# analog_pitch_board.net
KiCad netlist of a schematic drawn in EAGLE
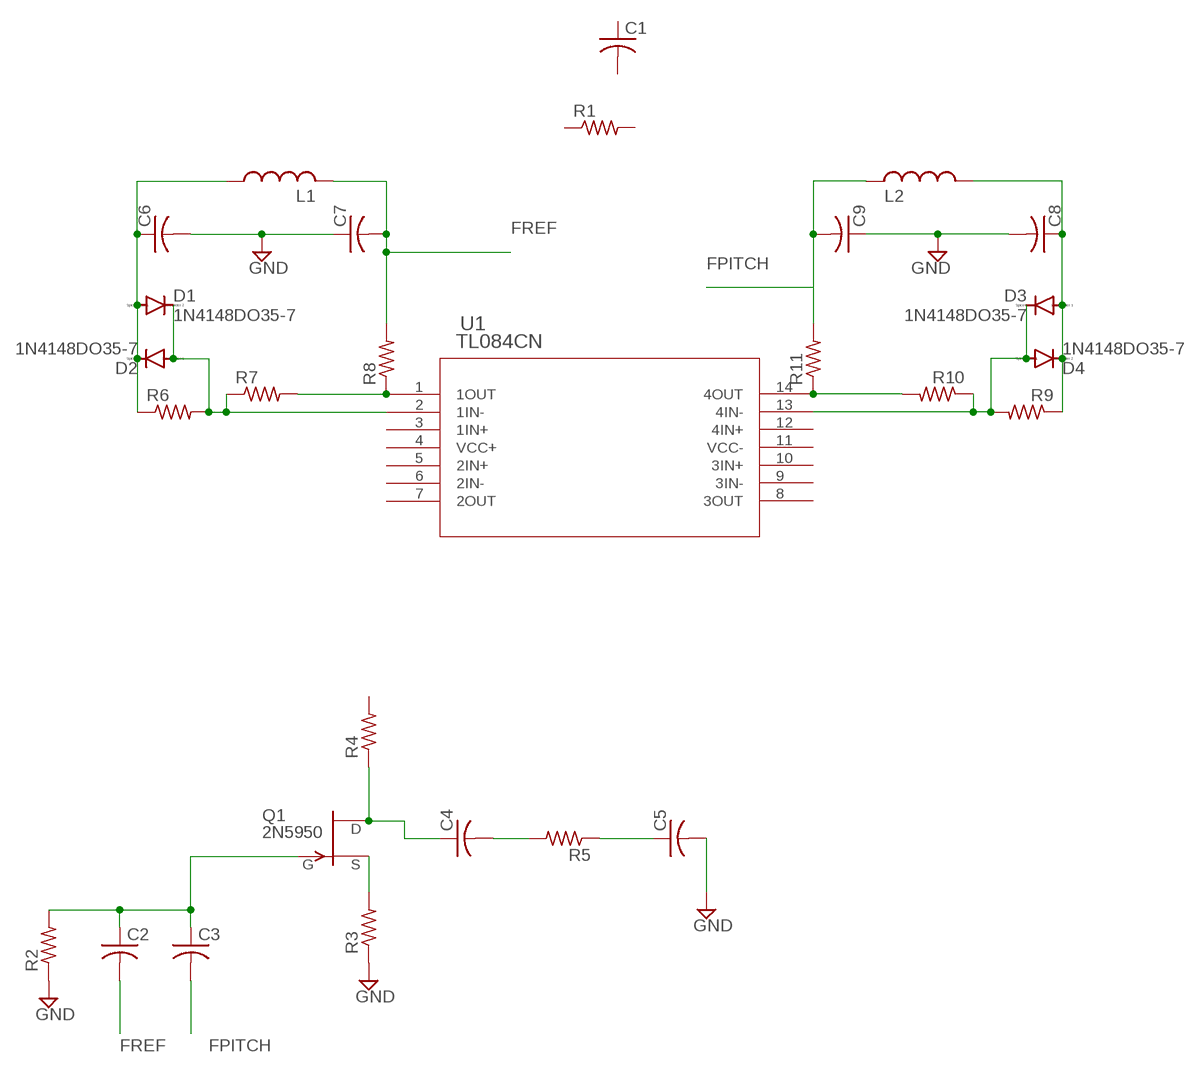
[diagram p0: schematic, sheet 1]

(export (version "E")
  (design (tool "Eeschema 10.0.6"))
  (components
    (comp (ref "C1")
      (value "C-US025-024X044")
      (footprint "eagle-import:C025-024X044")
      (libsource (lib "eagle-import") (part "C-US025-024X044"))
    )
    (comp (ref "C2")
      (value "C-US025-024X044")
      (footprint "eagle-import:C025-024X044")
      (libsource (lib "eagle-import") (part "C-US025-024X044"))
    )
    (comp (ref "C3")
      (value "C-US025-024X044")
      (footprint "eagle-import:C025-024X044")
      (libsource (lib "eagle-import") (part "C-US025-024X044"))
    )
    (comp (ref "C4")
      (value "C-US025-024X044")
      (footprint "eagle-import:C025-024X044")
      (libsource (lib "eagle-import") (part "C-US025-024X044"))
    )
    (comp (ref "C5")
      (value "C-US025-024X044")
      (footprint "eagle-import:C025-024X044")
      (libsource (lib "eagle-import") (part "C-US025-024X044"))
    )
    (comp (ref "C6")
      (value "C-US025-024X044")
      (footprint "eagle-import:C025-024X044")
      (libsource (lib "eagle-import") (part "C-US025-024X044"))
    )
    (comp (ref "C7")
      (value "C-US025-024X044")
      (footprint "eagle-import:C025-024X044")
      (libsource (lib "eagle-import") (part "C-US025-024X044"))
    )
    (comp (ref "C8")
      (value "C-US025-024X044")
      (footprint "eagle-import:C025-024X044")
      (libsource (lib "eagle-import") (part "C-US025-024X044"))
    )
    (comp (ref "C9")
      (value "C-US025-024X044")
      (footprint "eagle-import:C025-024X044")
      (libsource (lib "eagle-import") (part "C-US025-024X044"))
    )
    (comp (ref "D1")
      (value "1N4148DO35-7")
      (footprint "eagle-import:DO35-7")
      (libsource (lib "eagle-import") (part "1N4148DO35-7"))
    )
    (comp (ref "D2")
      (value "1N4148DO35-7")
      (footprint "eagle-import:DO35-7")
      (libsource (lib "eagle-import") (part "1N4148DO35-7"))
    )
    (comp (ref "D3")
      (value "1N4148DO35-7")
      (footprint "eagle-import:DO35-7")
      (libsource (lib "eagle-import") (part "1N4148DO35-7"))
    )
    (comp (ref "D4")
      (value "1N4148DO35-7")
      (footprint "eagle-import:DO35-7")
      (libsource (lib "eagle-import") (part "1N4148DO35-7"))
    )
    (comp (ref "L1")
      (value "L-US6000-XXX-RC")
      (footprint "eagle-import:6000-XXXX-RC")
      (libsource (lib "eagle-import") (part "L-US6000-XXX-RC"))
    )
    (comp (ref "L2")
      (value "L-US6000-XXX-RC")
      (footprint "eagle-import:6000-XXXX-RC")
      (libsource (lib "eagle-import") (part "L-US6000-XXX-RC"))
    )
    (comp (ref "Q1")
      (value "2N5950")
      (footprint "eagle-import:TO-92")
      (libsource (lib "eagle-import") (part "2N5950"))
    )
    (comp (ref "R1")
      (value "R-US_0207/10")
      (footprint "eagle-import:0207_10")
      (libsource (lib "eagle-import") (part "R-US_0207/10"))
    )
    (comp (ref "R2")
      (value "R-US_0207/10")
      (footprint "eagle-import:0207_10")
      (libsource (lib "eagle-import") (part "R-US_0207/10"))
    )
    (comp (ref "R3")
      (value "R-US_0207/10")
      (footprint "eagle-import:0207_10")
      (libsource (lib "eagle-import") (part "R-US_0207/10"))
    )
    (comp (ref "R4")
      (value "R-US_0207/10")
      (footprint "eagle-import:0207_10")
      (libsource (lib "eagle-import") (part "R-US_0207/10"))
    )
    (comp (ref "R5")
      (value "R-US_0207/10")
      (footprint "eagle-import:0207_10")
      (libsource (lib "eagle-import") (part "R-US_0207/10"))
    )
    (comp (ref "R6")
      (value "R-US_0207/10")
      (footprint "eagle-import:0207_10")
      (libsource (lib "eagle-import") (part "R-US_0207/10"))
    )
    (comp (ref "R7")
      (value "R-US_0207/10")
      (footprint "eagle-import:0207_10")
      (libsource (lib "eagle-import") (part "R-US_0207/10"))
    )
    (comp (ref "R8")
      (value "R-US_0207/10")
      (footprint "eagle-import:0207_10")
      (libsource (lib "eagle-import") (part "R-US_0207/10"))
    )
    (comp (ref "R9")
      (value "R-US_0207/10")
      (footprint "eagle-import:0207_10")
      (libsource (lib "eagle-import") (part "R-US_0207/10"))
    )
    (comp (ref "R10")
      (value "R-US_0207/10")
      (footprint "eagle-import:0207_10")
      (libsource (lib "eagle-import") (part "R-US_0207/10"))
    )
    (comp (ref "R11")
      (value "R-US_0207/10")
      (footprint "eagle-import:0207_10")
      (libsource (lib "eagle-import") (part "R-US_0207/10"))
    )
    (comp (ref "U1")
      (value "TL084CN")
      (footprint "eagle-import:N14")
      (fields (field (name "COPYRIGHT") "Copyright (C) 2025 Ultra Librarian. All rights reserved."))
      (libsource (lib "eagle-import") (part "TL084CN"))
    )
  )
  (nets
    (net (code "1") (name "/FPITCH") (class "Default")
      (node (ref "C3") (pin "2") (pinfunction "2_2") (pintype "passive"))
      (node (ref "C9") (pin "2") (pinfunction "2_2") (pintype "passive"))
      (node (ref "L2") (pin "2") (pinfunction "2_2") (pintype "passive"))
      (node (ref "R11") (pin "2") (pinfunction "2_2") (pintype "passive"))
    )
    (net (code "2") (name "/FREF") (class "Default")
      (node (ref "C2") (pin "2") (pinfunction "2_2") (pintype "passive"))
      (node (ref "C7") (pin "2") (pinfunction "2_2") (pintype "passive"))
      (node (ref "L1") (pin "2") (pinfunction "2_2") (pintype "passive"))
      (node (ref "R8") (pin "2") (pinfunction "2_2") (pintype "passive"))
    )
    (net (code "3") (name "/VCC+") (class "Default")
      (node (ref "U1") (pin "4") (pinfunction "VCC+_4") (pintype "power_in"))
    )
    (net (code "4") (name "/VCC-") (class "Default")
      (node (ref "U1") (pin "11") (pinfunction "VCC-_11") (pintype "power_in"))
    )
    (net (code "5") (name "GND") (class "Default")
      (node (ref "C5") (pin "2") (pinfunction "2_2") (pintype "passive"))
      (node (ref "C6") (pin "2") (pinfunction "2_2") (pintype "passive"))
      (node (ref "C7") (pin "1") (pinfunction "1_1") (pintype "passive"))
      (node (ref "C8") (pin "2") (pinfunction "2_2") (pintype "passive"))
      (node (ref "C9") (pin "1") (pinfunction "1_1") (pintype "passive"))
      (node (ref "R2") (pin "1") (pinfunction "1_1") (pintype "passive"))
      (node (ref "R3") (pin "1") (pinfunction "1_1") (pintype "passive"))
    )
    (net (code "6") (name "Net-(C4-Pad2)") (class "Default")
      (node (ref "C4") (pin "2") (pinfunction "2_2") (pintype "passive"))
      (node (ref "R5") (pin "2") (pinfunction "2_2") (pintype "passive"))
    )
    (net (code "7") (name "Net-(C5-Pad1)") (class "Default")
      (node (ref "C5") (pin "1") (pinfunction "1_1") (pintype "passive"))
      (node (ref "R5") (pin "1") (pinfunction "1_1") (pintype "passive"))
    )
    (net (code "8") (name "Net-(C6-Pad1)") (class "Default")
      (node (ref "C6") (pin "1") (pinfunction "1_1") (pintype "passive"))
      (node (ref "D1") (pin "A") (pinfunction "A_A") (pintype "passive"))
      (node (ref "D2") (pin "C") (pinfunction "C_C") (pintype "passive"))
      (node (ref "L1") (pin "1") (pinfunction "1_1") (pintype "passive"))
      (node (ref "R6") (pin "1") (pinfunction "1_1") (pintype "passive"))
    )
    (net (code "9") (name "Net-(C8-Pad1)") (class "Default")
      (node (ref "C8") (pin "1") (pinfunction "1_1") (pintype "passive"))
      (node (ref "D3") (pin "A") (pinfunction "A_A") (pintype "passive"))
      (node (ref "D4") (pin "C") (pinfunction "C_C") (pintype "passive"))
      (node (ref "L2") (pin "1") (pinfunction "1_1") (pintype "passive"))
      (node (ref "R9") (pin "1") (pinfunction "1_1") (pintype "passive"))
    )
    (net (code "10") (name "Net-(Q1-D)") (class "Default")
      (node (ref "C4") (pin "1") (pinfunction "1_1") (pintype "passive"))
      (node (ref "Q1") (pin "3") (pinfunction "D_3") (pintype "passive"))
      (node (ref "R4") (pin "1") (pinfunction "1_1") (pintype "passive"))
    )
    (net (code "11") (name "Net-(Q1-G)") (class "Default")
      (node (ref "C2") (pin "1") (pinfunction "1_1") (pintype "passive"))
      (node (ref "C3") (pin "1") (pinfunction "1_1") (pintype "passive"))
      (node (ref "Q1") (pin "1") (pinfunction "G_1") (pintype "passive"))
      (node (ref "R2") (pin "2") (pinfunction "2_2") (pintype "passive"))
    )
    (net (code "12") (name "Net-(Q1-S)") (class "Default")
      (node (ref "Q1") (pin "2") (pinfunction "S_2") (pintype "passive"))
      (node (ref "R3") (pin "2") (pinfunction "2_2") (pintype "passive"))
    )
    (net (code "13") (name "Net-(U1-1IN-)") (class "Default")
      (node (ref "D1") (pin "C") (pinfunction "C_C") (pintype "passive"))
      (node (ref "D2") (pin "A") (pinfunction "A_A") (pintype "passive"))
      (node (ref "R6") (pin "2") (pinfunction "2_2") (pintype "passive"))
      (node (ref "R7") (pin "1") (pinfunction "1_1") (pintype "passive"))
      (node (ref "U1") (pin "2") (pinfunction "1IN-_2") (pintype "input"))
    )
    (net (code "14") (name "Net-(U1-1OUT)") (class "Default")
      (node (ref "R7") (pin "2") (pinfunction "2_2") (pintype "passive"))
      (node (ref "R8") (pin "1") (pinfunction "1_1") (pintype "passive"))
      (node (ref "U1") (pin "1") (pinfunction "1OUT_1") (pintype "output"))
    )
    (net (code "15") (name "Net-(U1-4IN-)") (class "Default")
      (node (ref "D3") (pin "C") (pinfunction "C_C") (pintype "passive"))
      (node (ref "D4") (pin "A") (pinfunction "A_A") (pintype "passive"))
      (node (ref "R10") (pin "1") (pinfunction "1_1") (pintype "passive"))
      (node (ref "R9") (pin "2") (pinfunction "2_2") (pintype "passive"))
      (node (ref "U1") (pin "13") (pinfunction "4IN-_13") (pintype "input"))
    )
    (net (code "16") (name "Net-(U1-4OUT)") (class "Default")
      (node (ref "R10") (pin "2") (pinfunction "2_2") (pintype "passive"))
      (node (ref "R11") (pin "1") (pinfunction "1_1") (pintype "passive"))
      (node (ref "U1") (pin "14") (pinfunction "4OUT_14") (pintype "output"))
    )
    (net (code "17") (name "unconnected-(C1-Pad1)") (class "Default")
      (node (ref "C1") (pin "1") (pinfunction "1_1") (pintype "passive"))
    )
    (net (code "18") (name "unconnected-(C1-Pad2)") (class "Default")
      (node (ref "C1") (pin "2") (pinfunction "2_2") (pintype "passive"))
    )
    (net (code "19") (name "unconnected-(R1-Pad1)") (class "Default")
      (node (ref "R1") (pin "1") (pinfunction "1_1") (pintype "passive"))
    )
    (net (code "20") (name "unconnected-(R1-Pad2)") (class "Default")
      (node (ref "R1") (pin "2") (pinfunction "2_2") (pintype "passive"))
    )
    (net (code "21") (name "unconnected-(R4-Pad2)") (class "Default")
      (node (ref "R4") (pin "2") (pinfunction "2_2") (pintype "passive"))
    )
    (net (code "22") (name "unconnected-(U1-1IN+-Pad3)") (class "Default")
      (node (ref "U1") (pin "3") (pinfunction "1IN+_3") (pintype "input"))
    )
    (net (code "23") (name "unconnected-(U1-2IN+-Pad5)") (class "Default")
      (node (ref "U1") (pin "5") (pinfunction "2IN+_5") (pintype "input"))
    )
    (net (code "24") (name "unconnected-(U1-2IN--Pad6)") (class "Default")
      (node (ref "U1") (pin "6") (pinfunction "2IN-_6") (pintype "input"))
    )
    (net (code "25") (name "unconnected-(U1-2OUT-Pad7)") (class "Default")
      (node (ref "U1") (pin "7") (pinfunction "2OUT_7") (pintype "output"))
    )
    (net (code "26") (name "unconnected-(U1-3IN+-Pad10)") (class "Default")
      (node (ref "U1") (pin "10") (pinfunction "3IN+_10") (pintype "input"))
    )
    (net (code "27") (name "unconnected-(U1-3IN--Pad9)") (class "Default")
      (node (ref "U1") (pin "9") (pinfunction "3IN-_9") (pintype "input"))
    )
    (net (code "28") (name "unconnected-(U1-3OUT-Pad8)") (class "Default")
      (node (ref "U1") (pin "8") (pinfunction "3OUT_8") (pintype "output"))
    )
    (net (code "29") (name "unconnected-(U1-4IN+-Pad12)") (class "Default")
      (node (ref "U1") (pin "12") (pinfunction "4IN+_12") (pintype "input"))
    )
  )
)
